# co2_temp.net
KiCad netlist of a schematic drawn in EAGLE
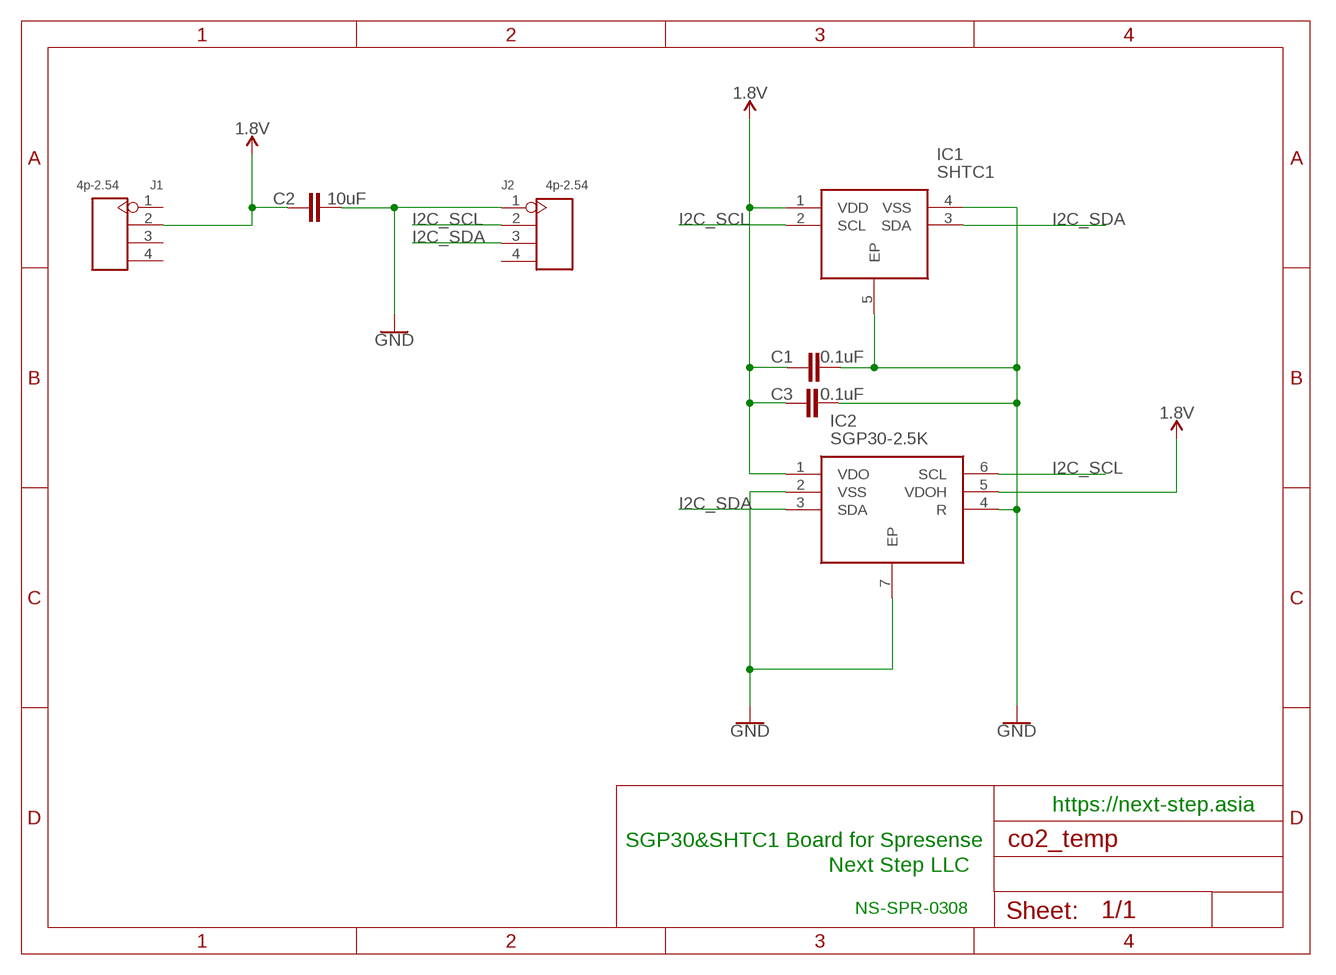
[diagram p0: schematic, sheet 1]

(export (version "E")
  (design (tool "Eeschema 10.0.6"))
  (components
    (comp (ref "C1")
      (value "0.1uF")
      (footprint "eagle-import:0603")
      (libsource (lib "eagle-import") (part "0.1UF-0603-25V-5%"))
    )
    (comp (ref "C2")
      (value "10uF")
      (footprint "eagle-import:0603")
      (libsource (lib "eagle-import") (part "10UF-0603-6.3V-20%"))
    )
    (comp (ref "C3")
      (value "0.1uF")
      (footprint "eagle-import:0603")
      (libsource (lib "eagle-import") (part "0.1UF-0603-25V-5%"))
    )
    (comp (ref "IC1")
      (value "SHTC1")
      (footprint "eagle-import:SON100P200X200X7500-5N")
      (fields (field (name "MOUSER_PART_NUMBER") "403-SHTC1"))
      (libsource (lib "eagle-import") (part "SHTC1"))
    )
    (comp (ref "IC2")
      (value "SGP30-2.5K")
      (footprint "eagle-import:SON80P245X245X90-7N")
      (fields
        (field (name "MANUFACTURER_PART_NUMBER") "SGP30-2.5k")
        (field (name "MOUSER_PART_NUMBER") "403-SGP30-2.5K")
      )
      (libsource (lib "eagle-import") (part "SGP30-2.5K"))
    )
    (comp (ref "J1")
      (value "4p-2.54")
      (footprint "eagle-import:H4-2.54")
      (fields (field (name "MPN") "F185-1104A1BSYA1"))
      (libsource (lib "eagle-import") (part "DIP-BLACK-FEMALE-HEADER-VERT(4P-2.54)"))
    )
    (comp (ref "J2")
      (value "4p-2.54")
      (footprint "eagle-import:H4-2.54")
      (fields (field (name "MPN") "F185-1104A1BSYA1"))
      (libsource (lib "eagle-import") (part "DIP-BLACK-FEMALE-HEADER-VERT(4P-2.54)"))
    )
  )
  (nets
    (net (code "1") (name "/I2C_SCL") (class "Default")
      (node (ref "IC1") (pin "2") (pinfunction "SCL_2") (pintype "bidirectional"))
      (node (ref "IC2") (pin "6") (pinfunction "SCL_6") (pintype "bidirectional"))
      (node (ref "J2") (pin "2") (pinfunction "P$2_2") (pintype "bidirectional"))
    )
    (net (code "2") (name "/I2C_SDA") (class "Default")
      (node (ref "IC1") (pin "3") (pinfunction "SDA_3") (pintype "bidirectional"))
      (node (ref "IC2") (pin "3") (pinfunction "SDA_3") (pintype "bidirectional"))
      (node (ref "J2") (pin "3") (pinfunction "P$3_3") (pintype "bidirectional"))
    )
    (net (code "3") (name "1.8V") (class "Default")
      (node (ref "C1") (pin "1") (pinfunction "1_1") (pintype "passive"))
      (node (ref "C2") (pin "1") (pinfunction "1_1") (pintype "passive"))
      (node (ref "C3") (pin "1") (pinfunction "1_1") (pintype "passive"))
      (node (ref "IC1") (pin "1") (pinfunction "VDD_1") (pintype "bidirectional"))
      (node (ref "IC2") (pin "1") (pinfunction "VDO_1") (pintype "power_in"))
      (node (ref "IC2") (pin "5") (pinfunction "VDOH_5") (pintype "power_in"))
      (node (ref "J1") (pin "2") (pinfunction "P$2_2") (pintype "bidirectional"))
    )
    (net (code "4") (name "GND") (class "Default")
      (node (ref "C1") (pin "2") (pinfunction "2_2") (pintype "passive"))
      (node (ref "C2") (pin "2") (pinfunction "2_2") (pintype "passive"))
      (node (ref "C3") (pin "2") (pinfunction "2_2") (pintype "passive"))
      (node (ref "IC1") (pin "4") (pinfunction "VSS_4") (pintype "bidirectional"))
      (node (ref "IC1") (pin "5") (pinfunction "EP_5") (pintype "bidirectional"))
      (node (ref "IC2") (pin "2") (pinfunction "VSS_2") (pintype "power_in"))
      (node (ref "IC2") (pin "4") (pinfunction "R_4") (pintype "power_in"))
      (node (ref "IC2") (pin "7") (pinfunction "EP_7") (pintype "bidirectional"))
      (node (ref "J2") (pin "1") (pinfunction "P$1_1") (pintype "bidirectional"))
    )
    (net (code "5") (name "unconnected-(J1-P$1-Pad1)") (class "Default")
      (node (ref "J1") (pin "1") (pinfunction "P$1_1") (pintype "bidirectional"))
    )
    (net (code "6") (name "unconnected-(J1-P$3-Pad3)") (class "Default")
      (node (ref "J1") (pin "3") (pinfunction "P$3_3") (pintype "bidirectional"))
    )
    (net (code "7") (name "unconnected-(J1-P$4-Pad4)") (class "Default")
      (node (ref "J1") (pin "4") (pinfunction "P$4_4") (pintype "bidirectional"))
    )
    (net (code "8") (name "unconnected-(J2-P$4-Pad4)") (class "Default")
      (node (ref "J2") (pin "4") (pinfunction "P$4_4") (pintype "bidirectional"))
    )
  )
)
